# X002X.net
KiCad netlist of a schematic drawn in EAGLE
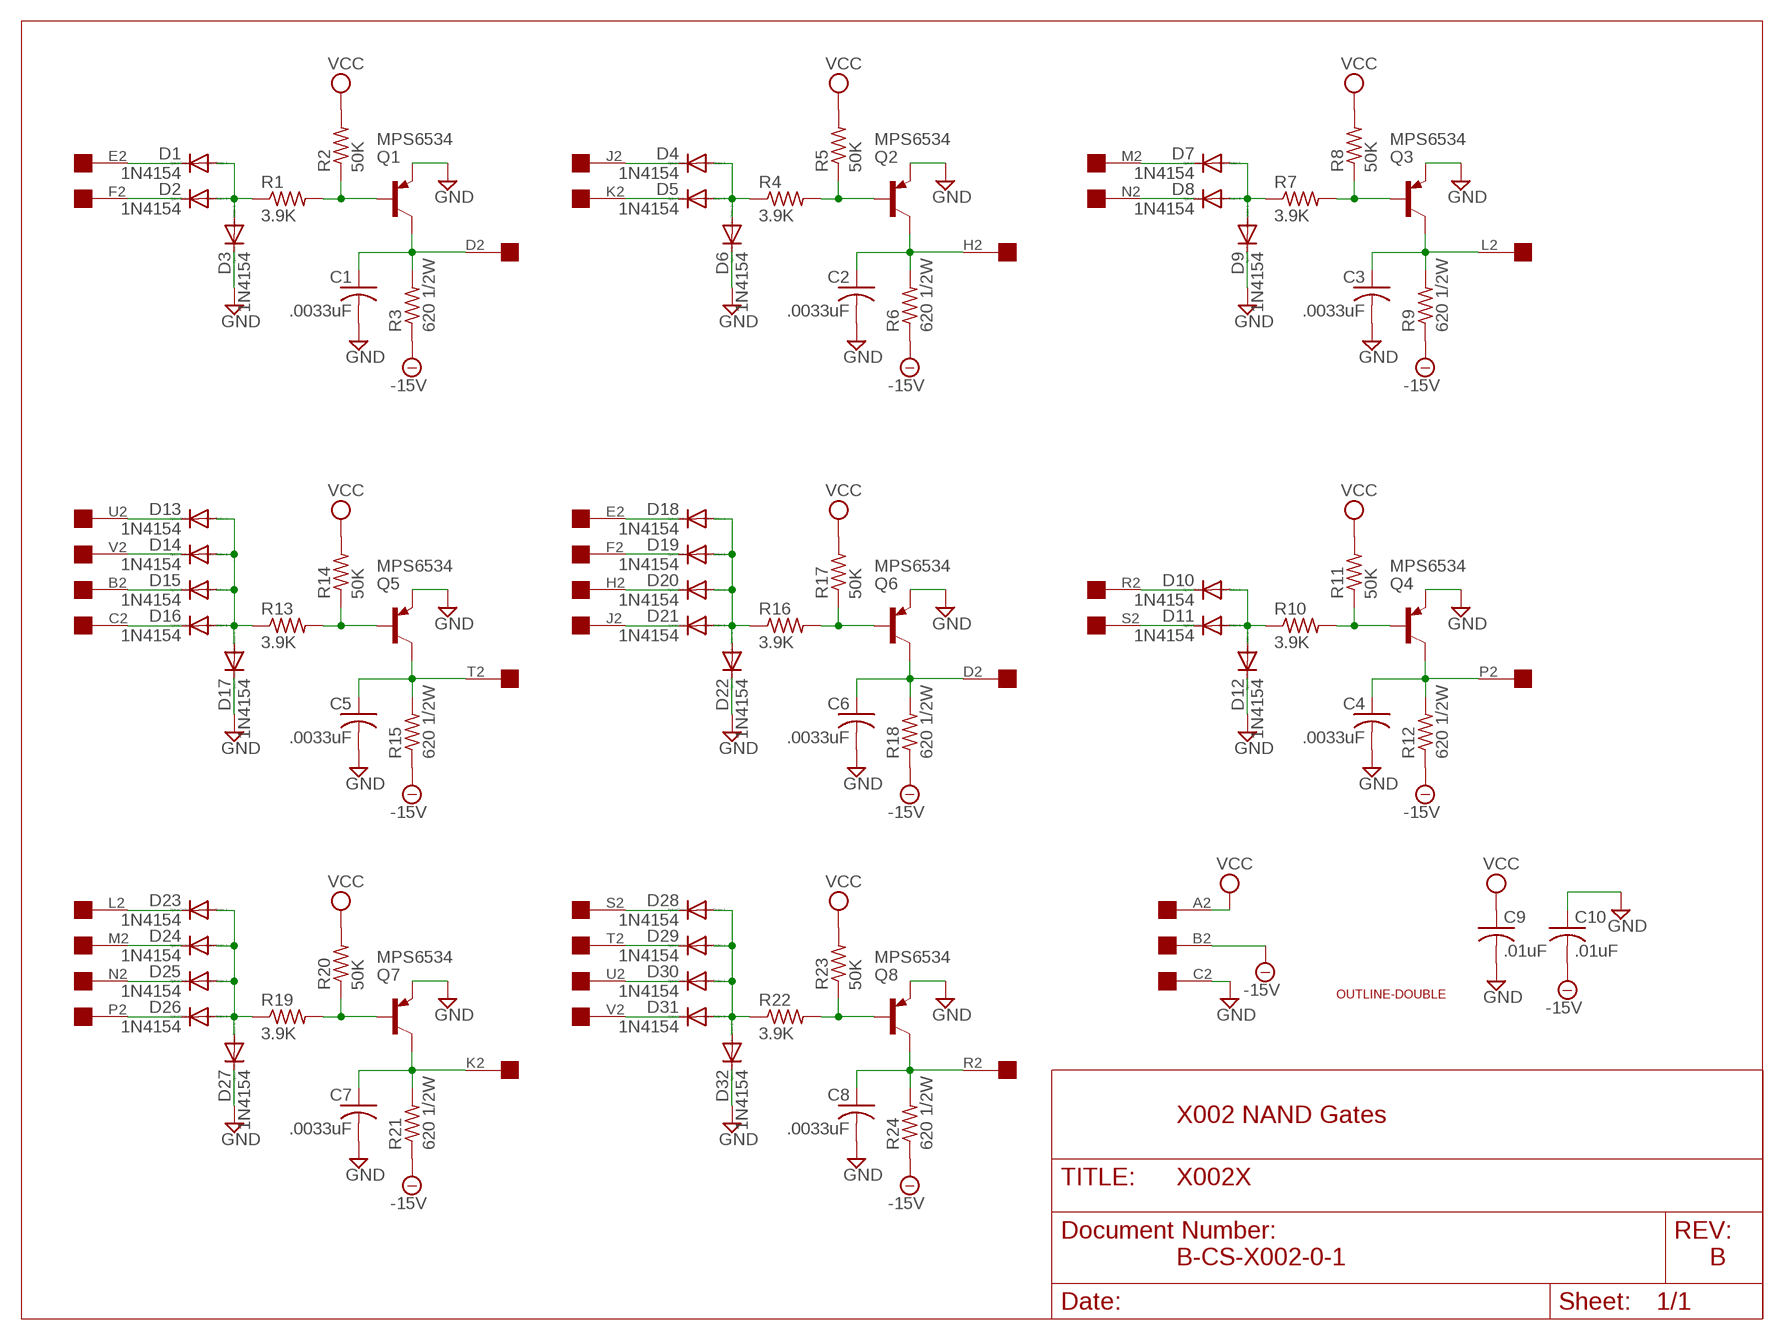
[diagram p0: schematic, sheet 1]

(export (version "E")
  (design (tool "Eeschema 10.0.6"))
  (components
    (comp (ref "A")
      (value "EDGE-1")
      (footprint "eagle-import:EDGE-CON1")
      (libsource (lib "eagle-import") (part "EDGE-1"))
    )
    (comp (ref "B")
      (value "EDGE-1")
      (footprint "eagle-import:EDGE-CON1")
      (libsource (lib "eagle-import") (part "EDGE-1"))
    )
    (comp (ref "C1")
      (value ".0033uF")
      (footprint "eagle-import:C225-062X268")
      (libsource (lib "eagle-import") (part "C-US225-062X268"))
    )
    (comp (ref "C2")
      (value ".0033uF")
      (footprint "eagle-import:C225-062X268")
      (libsource (lib "eagle-import") (part "C-US225-062X268"))
    )
    (comp (ref "C3")
      (value ".0033uF")
      (footprint "eagle-import:C225-062X268")
      (libsource (lib "eagle-import") (part "C-US225-062X268"))
    )
    (comp (ref "C4")
      (value ".0033uF")
      (footprint "eagle-import:C225-062X268")
      (libsource (lib "eagle-import") (part "C-US225-062X268"))
    )
    (comp (ref "C5")
      (value ".0033uF")
      (footprint "eagle-import:C225-062X268")
      (libsource (lib "eagle-import") (part "C-US225-062X268"))
    )
    (comp (ref "C6")
      (value ".0033uF")
      (footprint "eagle-import:C225-062X268")
      (libsource (lib "eagle-import") (part "C-US225-062X268"))
    )
    (comp (ref "C7")
      (value ".0033uF")
      (footprint "eagle-import:C225-062X268")
      (libsource (lib "eagle-import") (part "C-US225-062X268"))
    )
    (comp (ref "C8")
      (value ".0033uF")
      (footprint "eagle-import:C225-062X268")
      (libsource (lib "eagle-import") (part "C-US225-062X268"))
    )
    (comp (ref "C9")
      (value ".01uF")
      (footprint "eagle-import:C050-025X075")
      (libsource (lib "eagle-import") (part "C-US050-025X075"))
    )
    (comp (ref "C10")
      (value ".01uF")
      (footprint "eagle-import:C050-025X075")
      (libsource (lib "eagle-import") (part "C-US050-025X075"))
    )
    (comp (ref "D1")
      (value "1N4154")
      (footprint "eagle-import:DO35-10")
      (libsource (lib "eagle-import") (part "DIODE-DO35-10"))
    )
    (comp (ref "D2")
      (value "1N4154")
      (footprint "eagle-import:DO35-10")
      (libsource (lib "eagle-import") (part "DIODE-DO35-10"))
    )
    (comp (ref "D3")
      (value "1N4154")
      (footprint "eagle-import:DO35-10")
      (libsource (lib "eagle-import") (part "DIODE-DO35-10"))
    )
    (comp (ref "D4")
      (value "1N4154")
      (footprint "eagle-import:DO35-10")
      (libsource (lib "eagle-import") (part "DIODE-DO35-10"))
    )
    (comp (ref "D5")
      (value "1N4154")
      (footprint "eagle-import:DO35-10")
      (libsource (lib "eagle-import") (part "DIODE-DO35-10"))
    )
    (comp (ref "D6")
      (value "1N4154")
      (footprint "eagle-import:DO35-10")
      (libsource (lib "eagle-import") (part "DIODE-DO35-10"))
    )
    (comp (ref "D7")
      (value "1N4154")
      (footprint "eagle-import:DO35-10")
      (libsource (lib "eagle-import") (part "DIODE-DO35-10"))
    )
    (comp (ref "D8")
      (value "1N4154")
      (footprint "eagle-import:DO35-10")
      (libsource (lib "eagle-import") (part "DIODE-DO35-10"))
    )
    (comp (ref "D9")
      (value "1N4154")
      (footprint "eagle-import:DO35-10")
      (libsource (lib "eagle-import") (part "DIODE-DO35-10"))
    )
    (comp (ref "D10")
      (value "1N4154")
      (footprint "eagle-import:DO35-10")
      (libsource (lib "eagle-import") (part "DIODE-DO35-10"))
    )
    (comp (ref "D11")
      (value "1N4154")
      (footprint "eagle-import:DO35-10")
      (libsource (lib "eagle-import") (part "DIODE-DO35-10"))
    )
    (comp (ref "D12")
      (value "1N4154")
      (footprint "eagle-import:DO35-10")
      (libsource (lib "eagle-import") (part "DIODE-DO35-10"))
    )
    (comp (ref "D13")
      (value "1N4154")
      (footprint "eagle-import:DO35-10")
      (libsource (lib "eagle-import") (part "DIODE-DO35-10"))
    )
    (comp (ref "D14")
      (value "1N4154")
      (footprint "eagle-import:DO35-10")
      (libsource (lib "eagle-import") (part "DIODE-DO35-10"))
    )
    (comp (ref "D15")
      (value "1N4154")
      (footprint "eagle-import:DO35-10")
      (libsource (lib "eagle-import") (part "DIODE-DO35-10"))
    )
    (comp (ref "D16")
      (value "1N4154")
      (footprint "eagle-import:DO35-10")
      (libsource (lib "eagle-import") (part "DIODE-DO35-10"))
    )
    (comp (ref "D17")
      (value "1N4154")
      (footprint "eagle-import:DO35-10")
      (libsource (lib "eagle-import") (part "DIODE-DO35-10"))
    )
    (comp (ref "D18")
      (value "1N4154")
      (footprint "eagle-import:DO35-10")
      (libsource (lib "eagle-import") (part "DIODE-DO35-10"))
    )
    (comp (ref "D19")
      (value "1N4154")
      (footprint "eagle-import:DO35-10")
      (libsource (lib "eagle-import") (part "DIODE-DO35-10"))
    )
    (comp (ref "D20")
      (value "1N4154")
      (footprint "eagle-import:DO35-10")
      (libsource (lib "eagle-import") (part "DIODE-DO35-10"))
    )
    (comp (ref "D21")
      (value "1N4154")
      (footprint "eagle-import:DO35-10")
      (libsource (lib "eagle-import") (part "DIODE-DO35-10"))
    )
    (comp (ref "D22")
      (value "1N4154")
      (footprint "eagle-import:DO35-10")
      (libsource (lib "eagle-import") (part "DIODE-DO35-10"))
    )
    (comp (ref "D23")
      (value "1N4154")
      (footprint "eagle-import:DO35-10")
      (libsource (lib "eagle-import") (part "DIODE-DO35-10"))
    )
    (comp (ref "D24")
      (value "1N4154")
      (footprint "eagle-import:DO35-10")
      (libsource (lib "eagle-import") (part "DIODE-DO35-10"))
    )
    (comp (ref "D25")
      (value "1N4154")
      (footprint "eagle-import:DO35-10")
      (libsource (lib "eagle-import") (part "DIODE-DO35-10"))
    )
    (comp (ref "D26")
      (value "1N4154")
      (footprint "eagle-import:DO35-10")
      (libsource (lib "eagle-import") (part "DIODE-DO35-10"))
    )
    (comp (ref "D27")
      (value "1N4154")
      (footprint "eagle-import:DO35-10")
      (libsource (lib "eagle-import") (part "DIODE-DO35-10"))
    )
    (comp (ref "D28")
      (value "1N4154")
      (footprint "eagle-import:DO35-10")
      (libsource (lib "eagle-import") (part "DIODE-DO35-10"))
    )
    (comp (ref "D29")
      (value "1N4154")
      (footprint "eagle-import:DO35-10")
      (libsource (lib "eagle-import") (part "DIODE-DO35-10"))
    )
    (comp (ref "D30")
      (value "1N4154")
      (footprint "eagle-import:DO35-10")
      (libsource (lib "eagle-import") (part "DIODE-DO35-10"))
    )
    (comp (ref "D31")
      (value "1N4154")
      (footprint "eagle-import:DO35-10")
      (libsource (lib "eagle-import") (part "DIODE-DO35-10"))
    )
    (comp (ref "D32")
      (value "1N4154")
      (footprint "eagle-import:DO35-10")
      (libsource (lib "eagle-import") (part "DIODE-DO35-10"))
    )
    (comp (ref "Q1")
      (value "MPS6534")
      (footprint "eagle-import:TO5")
      (libsource (lib "eagle-import") (part "-PNP-TO5"))
    )
    (comp (ref "Q2")
      (value "MPS6534")
      (footprint "eagle-import:TO5")
      (libsource (lib "eagle-import") (part "-PNP-TO5"))
    )
    (comp (ref "Q3")
      (value "MPS6534")
      (footprint "eagle-import:TO5")
      (libsource (lib "eagle-import") (part "-PNP-TO5"))
    )
    (comp (ref "Q4")
      (value "MPS6534")
      (footprint "eagle-import:TO5")
      (libsource (lib "eagle-import") (part "-PNP-TO5"))
    )
    (comp (ref "Q5")
      (value "MPS6534")
      (footprint "eagle-import:TO5")
      (libsource (lib "eagle-import") (part "-PNP-TO5"))
    )
    (comp (ref "Q6")
      (value "MPS6534")
      (footprint "eagle-import:TO5")
      (libsource (lib "eagle-import") (part "-PNP-TO5"))
    )
    (comp (ref "Q7")
      (value "MPS6534")
      (footprint "eagle-import:TO5")
      (libsource (lib "eagle-import") (part "-PNP-TO5"))
    )
    (comp (ref "Q8")
      (value "MPS6534")
      (footprint "eagle-import:TO5")
      (libsource (lib "eagle-import") (part "-PNP-TO5"))
    )
    (comp (ref "R1")
      (value "3.9K")
      (footprint "eagle-import:0207_10")
      (libsource (lib "eagle-import") (part "R-US_0207/10"))
    )
    (comp (ref "R2")
      (value "50K")
      (footprint "eagle-import:0207_10")
      (libsource (lib "eagle-import") (part "R-US_0207/10"))
    )
    (comp (ref "R3")
      (value "620 1/2W")
      (footprint "eagle-import:0414_15")
      (libsource (lib "eagle-import") (part "R-US_0414/15"))
    )
    (comp (ref "R4")
      (value "3.9K")
      (footprint "eagle-import:0207_10")
      (libsource (lib "eagle-import") (part "R-US_0207/10"))
    )
    (comp (ref "R5")
      (value "50K")
      (footprint "eagle-import:0207_10")
      (libsource (lib "eagle-import") (part "R-US_0207/10"))
    )
    (comp (ref "R6")
      (value "620 1/2W")
      (footprint "eagle-import:0414_15")
      (libsource (lib "eagle-import") (part "R-US_0414/15"))
    )
    (comp (ref "R7")
      (value "3.9K")
      (footprint "eagle-import:0207_10")
      (libsource (lib "eagle-import") (part "R-US_0207/10"))
    )
    (comp (ref "R8")
      (value "50K")
      (footprint "eagle-import:0207_10")
      (libsource (lib "eagle-import") (part "R-US_0207/10"))
    )
    (comp (ref "R9")
      (value "620 1/2W")
      (footprint "eagle-import:0414_15")
      (libsource (lib "eagle-import") (part "R-US_0414/15"))
    )
    (comp (ref "R10")
      (value "3.9K")
      (footprint "eagle-import:0207_10")
      (libsource (lib "eagle-import") (part "R-US_0207/10"))
    )
    (comp (ref "R11")
      (value "50K")
      (footprint "eagle-import:0207_10")
      (libsource (lib "eagle-import") (part "R-US_0207/10"))
    )
    (comp (ref "R12")
      (value "620 1/2W")
      (footprint "eagle-import:0414_15")
      (libsource (lib "eagle-import") (part "R-US_0414/15"))
    )
    (comp (ref "R13")
      (value "3.9K")
      (footprint "eagle-import:0207_10")
      (libsource (lib "eagle-import") (part "R-US_0207/10"))
    )
    (comp (ref "R14")
      (value "50K")
      (footprint "eagle-import:0207_10")
      (libsource (lib "eagle-import") (part "R-US_0207/10"))
    )
    (comp (ref "R15")
      (value "620 1/2W")
      (footprint "eagle-import:0414_15")
      (libsource (lib "eagle-import") (part "R-US_0414/15"))
    )
    (comp (ref "R16")
      (value "3.9K")
      (footprint "eagle-import:0207_10")
      (libsource (lib "eagle-import") (part "R-US_0207/10"))
    )
    (comp (ref "R17")
      (value "50K")
      (footprint "eagle-import:0207_10")
      (libsource (lib "eagle-import") (part "R-US_0207/10"))
    )
    (comp (ref "R18")
      (value "620 1/2W")
      (footprint "eagle-import:0414_15")
      (libsource (lib "eagle-import") (part "R-US_0414/15"))
    )
    (comp (ref "R19")
      (value "3.9K")
      (footprint "eagle-import:0207_10")
      (libsource (lib "eagle-import") (part "R-US_0207/10"))
    )
    (comp (ref "R20")
      (value "50K")
      (footprint "eagle-import:0207_10")
      (libsource (lib "eagle-import") (part "R-US_0207/10"))
    )
    (comp (ref "R21")
      (value "620 1/2W")
      (footprint "eagle-import:0414_15")
      (libsource (lib "eagle-import") (part "R-US_0414/15"))
    )
    (comp (ref "R22")
      (value "3.9K")
      (footprint "eagle-import:0207_10")
      (libsource (lib "eagle-import") (part "R-US_0207/10"))
    )
    (comp (ref "R23")
      (value "50K")
      (footprint "eagle-import:0207_10")
      (libsource (lib "eagle-import") (part "R-US_0207/10"))
    )
    (comp (ref "R24")
      (value "620 1/2W")
      (footprint "eagle-import:0414_15")
      (libsource (lib "eagle-import") (part "R-US_0414/15"))
    )
    (comp (ref "U$1")
      (value "OUTLINE-DOUBLE")
      (footprint "eagle-import:DOUBLE")
      (libsource (lib "eagle-import") (part "OUTLINE-DOUBLE"))
    )
  )
  (nets
    (net (code "1") (name "-15V") (class "Default")
      (node (ref "A") (pin "B2") (pinfunction "1_B2") (pintype "bidirectional"))
      (node (ref "C10") (pin "2") (pinfunction "2_2") (pintype "passive"))
      (node (ref "R12") (pin "1") (pinfunction "1_1") (pintype "passive"))
      (node (ref "R15") (pin "1") (pinfunction "1_1") (pintype "passive"))
      (node (ref "R18") (pin "1") (pinfunction "1_1") (pintype "passive"))
      (node (ref "R21") (pin "1") (pinfunction "1_1") (pintype "passive"))
      (node (ref "R24") (pin "1") (pinfunction "1_1") (pintype "passive"))
      (node (ref "R3") (pin "1") (pinfunction "1_1") (pintype "passive"))
      (node (ref "R6") (pin "1") (pinfunction "1_1") (pintype "passive"))
      (node (ref "R9") (pin "1") (pinfunction "1_1") (pintype "passive"))
    )
    (net (code "2") (name "GND") (class "Default")
      (node (ref "A") (pin "C2") (pinfunction "1_C2") (pintype "bidirectional"))
      (node (ref "C1") (pin "2") (pinfunction "2_2") (pintype "passive"))
      (node (ref "C10") (pin "1") (pinfunction "1_1") (pintype "passive"))
      (node (ref "C2") (pin "2") (pinfunction "2_2") (pintype "passive"))
      (node (ref "C3") (pin "2") (pinfunction "2_2") (pintype "passive"))
      (node (ref "C4") (pin "2") (pinfunction "2_2") (pintype "passive"))
      (node (ref "C5") (pin "2") (pinfunction "2_2") (pintype "passive"))
      (node (ref "C6") (pin "2") (pinfunction "2_2") (pintype "passive"))
      (node (ref "C7") (pin "2") (pinfunction "2_2") (pintype "passive"))
      (node (ref "C8") (pin "2") (pinfunction "2_2") (pintype "passive"))
      (node (ref "C9") (pin "2") (pinfunction "2_2") (pintype "passive"))
      (node (ref "D12") (pin "C") (pinfunction "C_C") (pintype "passive"))
      (node (ref "D17") (pin "C") (pinfunction "C_C") (pintype "passive"))
      (node (ref "D22") (pin "C") (pinfunction "C_C") (pintype "passive"))
      (node (ref "D27") (pin "C") (pinfunction "C_C") (pintype "passive"))
      (node (ref "D3") (pin "C") (pinfunction "C_C") (pintype "passive"))
      (node (ref "D32") (pin "C") (pinfunction "C_C") (pintype "passive"))
      (node (ref "D6") (pin "C") (pinfunction "C_C") (pintype "passive"))
      (node (ref "D9") (pin "C") (pinfunction "C_C") (pintype "passive"))
      (node (ref "Q1") (pin "1") (pinfunction "E_1") (pintype "passive"))
      (node (ref "Q2") (pin "1") (pinfunction "E_1") (pintype "passive"))
      (node (ref "Q3") (pin "1") (pinfunction "E_1") (pintype "passive"))
      (node (ref "Q4") (pin "1") (pinfunction "E_1") (pintype "passive"))
      (node (ref "Q5") (pin "1") (pinfunction "E_1") (pintype "passive"))
      (node (ref "Q6") (pin "1") (pinfunction "E_1") (pintype "passive"))
      (node (ref "Q7") (pin "1") (pinfunction "E_1") (pintype "passive"))
      (node (ref "Q8") (pin "1") (pinfunction "E_1") (pintype "passive"))
    )
    (net (code "3") (name "Net-(AD-1)") (class "Default")
      (node (ref "A") (pin "D2") (pinfunction "1_D2") (pintype "bidirectional"))
      (node (ref "C1") (pin "1") (pinfunction "1_1") (pintype "passive"))
      (node (ref "Q1") (pin "3") (pinfunction "C_3") (pintype "passive"))
      (node (ref "R3") (pin "2") (pinfunction "2_2") (pintype "passive"))
    )
    (net (code "4") (name "Net-(AE-1)") (class "Default")
      (node (ref "A") (pin "E2") (pinfunction "1_E2") (pintype "bidirectional"))
      (node (ref "D1") (pin "C") (pinfunction "C_C") (pintype "passive"))
    )
    (net (code "5") (name "Net-(AF-1)") (class "Default")
      (node (ref "A") (pin "F2") (pinfunction "1_F2") (pintype "bidirectional"))
      (node (ref "D2") (pin "C") (pinfunction "C_C") (pintype "passive"))
    )
    (net (code "6") (name "Net-(AG-1)") (class "Default")
      (node (ref "A") (pin "H2") (pinfunction "1_H2") (pintype "bidirectional"))
      (node (ref "C2") (pin "1") (pinfunction "1_1") (pintype "passive"))
      (node (ref "Q2") (pin "3") (pinfunction "C_3") (pintype "passive"))
      (node (ref "R6") (pin "2") (pinfunction "2_2") (pintype "passive"))
    )
    (net (code "7") (name "Net-(AH-1)") (class "Default")
      (node (ref "A") (pin "J2") (pinfunction "1_J2") (pintype "bidirectional"))
      (node (ref "D4") (pin "C") (pinfunction "C_C") (pintype "passive"))
    )
    (net (code "8") (name "Net-(AI-1)") (class "Default")
      (node (ref "A") (pin "K2") (pinfunction "1_K2") (pintype "bidirectional"))
      (node (ref "D5") (pin "C") (pinfunction "C_C") (pintype "passive"))
    )
    (net (code "9") (name "Net-(AJ-1)") (class "Default")
      (node (ref "A") (pin "L2") (pinfunction "1_L2") (pintype "bidirectional"))
      (node (ref "C3") (pin "1") (pinfunction "1_1") (pintype "passive"))
      (node (ref "Q3") (pin "3") (pinfunction "C_3") (pintype "passive"))
      (node (ref "R9") (pin "2") (pinfunction "2_2") (pintype "passive"))
    )
    (net (code "10") (name "Net-(AK-1)") (class "Default")
      (node (ref "A") (pin "M2") (pinfunction "1_M2") (pintype "bidirectional"))
      (node (ref "D7") (pin "C") (pinfunction "C_C") (pintype "passive"))
    )
    (net (code "11") (name "Net-(AL-1)") (class "Default")
      (node (ref "A") (pin "N2") (pinfunction "1_N2") (pintype "bidirectional"))
      (node (ref "D8") (pin "C") (pinfunction "C_C") (pintype "passive"))
    )
    (net (code "12") (name "Net-(AM-1)") (class "Default")
      (node (ref "A") (pin "P2") (pinfunction "1_P2") (pintype "bidirectional"))
      (node (ref "C4") (pin "1") (pinfunction "1_1") (pintype "passive"))
      (node (ref "Q4") (pin "3") (pinfunction "C_3") (pintype "passive"))
      (node (ref "R12") (pin "2") (pinfunction "2_2") (pintype "passive"))
    )
    (net (code "13") (name "Net-(AN-1)") (class "Default")
      (node (ref "A") (pin "R2") (pinfunction "1_R2") (pintype "bidirectional"))
      (node (ref "D10") (pin "C") (pinfunction "C_C") (pintype "passive"))
    )
    (net (code "14") (name "Net-(AO-1)") (class "Default")
      (node (ref "A") (pin "S2") (pinfunction "1_S2") (pintype "bidirectional"))
      (node (ref "D11") (pin "C") (pinfunction "C_C") (pintype "passive"))
    )
    (net (code "15") (name "Net-(AP-1)") (class "Default")
      (node (ref "A") (pin "T2") (pinfunction "1_T2") (pintype "bidirectional"))
      (node (ref "C5") (pin "1") (pinfunction "1_1") (pintype "passive"))
      (node (ref "Q5") (pin "3") (pinfunction "C_3") (pintype "passive"))
      (node (ref "R15") (pin "2") (pinfunction "2_2") (pintype "passive"))
    )
    (net (code "16") (name "Net-(AQ-1)") (class "Default")
      (node (ref "A") (pin "U2") (pinfunction "1_U2") (pintype "bidirectional"))
      (node (ref "D13") (pin "C") (pinfunction "C_C") (pintype "passive"))
    )
    (net (code "17") (name "Net-(AR-1)") (class "Default")
      (node (ref "A") (pin "V2") (pinfunction "1_V2") (pintype "bidirectional"))
      (node (ref "D14") (pin "C") (pinfunction "C_C") (pintype "passive"))
    )
    (net (code "18") (name "Net-(BB-1)") (class "Default")
      (node (ref "B") (pin "B2") (pinfunction "1_B2") (pintype "bidirectional"))
      (node (ref "D15") (pin "C") (pinfunction "C_C") (pintype "passive"))
    )
    (net (code "19") (name "Net-(BC-1)") (class "Default")
      (node (ref "B") (pin "C2") (pinfunction "1_C2") (pintype "bidirectional"))
      (node (ref "D16") (pin "C") (pinfunction "C_C") (pintype "passive"))
    )
    (net (code "20") (name "Net-(BD-1)") (class "Default")
      (node (ref "B") (pin "D2") (pinfunction "1_D2") (pintype "bidirectional"))
      (node (ref "C6") (pin "1") (pinfunction "1_1") (pintype "passive"))
      (node (ref "Q6") (pin "3") (pinfunction "C_3") (pintype "passive"))
      (node (ref "R18") (pin "2") (pinfunction "2_2") (pintype "passive"))
    )
    (net (code "21") (name "Net-(BE-1)") (class "Default")
      (node (ref "B") (pin "E2") (pinfunction "1_E2") (pintype "bidirectional"))
      (node (ref "D18") (pin "C") (pinfunction "C_C") (pintype "passive"))
    )
    (net (code "22") (name "Net-(BF-1)") (class "Default")
      (node (ref "B") (pin "F2") (pinfunction "1_F2") (pintype "bidirectional"))
      (node (ref "D19") (pin "C") (pinfunction "C_C") (pintype "passive"))
    )
    (net (code "23") (name "Net-(BG-1)") (class "Default")
      (node (ref "B") (pin "H2") (pinfunction "1_H2") (pintype "bidirectional"))
      (node (ref "D20") (pin "C") (pinfunction "C_C") (pintype "passive"))
    )
    (net (code "24") (name "Net-(BH-1)") (class "Default")
      (node (ref "B") (pin "J2") (pinfunction "1_J2") (pintype "bidirectional"))
      (node (ref "D21") (pin "C") (pinfunction "C_C") (pintype "passive"))
    )
    (net (code "25") (name "Net-(BI-1)") (class "Default")
      (node (ref "B") (pin "K2") (pinfunction "1_K2") (pintype "bidirectional"))
      (node (ref "C7") (pin "1") (pinfunction "1_1") (pintype "passive"))
      (node (ref "Q7") (pin "3") (pinfunction "C_3") (pintype "passive"))
      (node (ref "R21") (pin "2") (pinfunction "2_2") (pintype "passive"))
    )
    (net (code "26") (name "Net-(BJ-1)") (class "Default")
      (node (ref "B") (pin "L2") (pinfunction "1_L2") (pintype "bidirectional"))
      (node (ref "D23") (pin "C") (pinfunction "C_C") (pintype "passive"))
    )
    (net (code "27") (name "Net-(BK-1)") (class "Default")
      (node (ref "B") (pin "M2") (pinfunction "1_M2") (pintype "bidirectional"))
      (node (ref "D24") (pin "C") (pinfunction "C_C") (pintype "passive"))
    )
    (net (code "28") (name "Net-(BL-1)") (class "Default")
      (node (ref "B") (pin "N2") (pinfunction "1_N2") (pintype "bidirectional"))
      (node (ref "D25") (pin "C") (pinfunction "C_C") (pintype "passive"))
    )
    (net (code "29") (name "Net-(BM-1)") (class "Default")
      (node (ref "B") (pin "P2") (pinfunction "1_P2") (pintype "bidirectional"))
      (node (ref "D26") (pin "C") (pinfunction "C_C") (pintype "passive"))
    )
    (net (code "30") (name "Net-(BN-1)") (class "Default")
      (node (ref "B") (pin "R2") (pinfunction "1_R2") (pintype "bidirectional"))
      (node (ref "C8") (pin "1") (pinfunction "1_1") (pintype "passive"))
      (node (ref "Q8") (pin "3") (pinfunction "C_3") (pintype "passive"))
      (node (ref "R24") (pin "2") (pinfunction "2_2") (pintype "passive"))
    )
    (net (code "31") (name "Net-(BO-1)") (class "Default")
      (node (ref "B") (pin "S2") (pinfunction "1_S2") (pintype "bidirectional"))
      (node (ref "D28") (pin "C") (pinfunction "C_C") (pintype "passive"))
    )
    (net (code "32") (name "Net-(BP-1)") (class "Default")
      (node (ref "B") (pin "T2") (pinfunction "1_T2") (pintype "bidirectional"))
      (node (ref "D29") (pin "C") (pinfunction "C_C") (pintype "passive"))
    )
    (net (code "33") (name "Net-(BQ-1)") (class "Default")
      (node (ref "B") (pin "U2") (pinfunction "1_U2") (pintype "bidirectional"))
      (node (ref "D30") (pin "C") (pinfunction "C_C") (pintype "passive"))
    )
    (net (code "34") (name "Net-(BR-1)") (class "Default")
      (node (ref "B") (pin "V2") (pinfunction "1_V2") (pintype "bidirectional"))
      (node (ref "D31") (pin "C") (pinfunction "C_C") (pintype "passive"))
    )
    (net (code "35") (name "Net-(D1-PadA)") (class "Default")
      (node (ref "D1") (pin "A") (pinfunction "A_A") (pintype "passive"))
      (node (ref "D2") (pin "A") (pinfunction "A_A") (pintype "passive"))
      (node (ref "D3") (pin "A") (pinfunction "A_A") (pintype "passive"))
      (node (ref "R1") (pin "1") (pinfunction "1_1") (pintype "passive"))
    )
    (net (code "36") (name "Net-(D4-PadA)") (class "Default")
      (node (ref "D4") (pin "A") (pinfunction "A_A") (pintype "passive"))
      (node (ref "D5") (pin "A") (pinfunction "A_A") (pintype "passive"))
      (node (ref "D6") (pin "A") (pinfunction "A_A") (pintype "passive"))
      (node (ref "R4") (pin "1") (pinfunction "1_1") (pintype "passive"))
    )
    (net (code "37") (name "Net-(D7-PadA)") (class "Default")
      (node (ref "D7") (pin "A") (pinfunction "A_A") (pintype "passive"))
      (node (ref "D8") (pin "A") (pinfunction "A_A") (pintype "passive"))
      (node (ref "D9") (pin "A") (pinfunction "A_A") (pintype "passive"))
      (node (ref "R7") (pin "1") (pinfunction "1_1") (pintype "passive"))
    )
    (net (code "38") (name "Net-(D10-PadA)") (class "Default")
      (node (ref "D10") (pin "A") (pinfunction "A_A") (pintype "passive"))
      (node (ref "D11") (pin "A") (pinfunction "A_A") (pintype "passive"))
      (node (ref "D12") (pin "A") (pinfunction "A_A") (pintype "passive"))
      (node (ref "R10") (pin "1") (pinfunction "1_1") (pintype "passive"))
    )
    (net (code "39") (name "Net-(D13-PadA)") (class "Default")
      (node (ref "D13") (pin "A") (pinfunction "A_A") (pintype "passive"))
      (node (ref "D14") (pin "A") (pinfunction "A_A") (pintype "passive"))
      (node (ref "D15") (pin "A") (pinfunction "A_A") (pintype "passive"))
      (node (ref "D16") (pin "A") (pinfunction "A_A") (pintype "passive"))
      (node (ref "D17") (pin "A") (pinfunction "A_A") (pintype "passive"))
      (node (ref "R13") (pin "1") (pinfunction "1_1") (pintype "passive"))
    )
    (net (code "40") (name "Net-(D18-PadA)") (class "Default")
      (node (ref "D18") (pin "A") (pinfunction "A_A") (pintype "passive"))
      (node (ref "D19") (pin "A") (pinfunction "A_A") (pintype "passive"))
      (node (ref "D20") (pin "A") (pinfunction "A_A") (pintype "passive"))
      (node (ref "D21") (pin "A") (pinfunction "A_A") (pintype "passive"))
      (node (ref "D22") (pin "A") (pinfunction "A_A") (pintype "passive"))
      (node (ref "R16") (pin "1") (pinfunction "1_1") (pintype "passive"))
    )
    (net (code "41") (name "Net-(D23-PadA)") (class "Default")
      (node (ref "D23") (pin "A") (pinfunction "A_A") (pintype "passive"))
      (node (ref "D24") (pin "A") (pinfunction "A_A") (pintype "passive"))
      (node (ref "D25") (pin "A") (pinfunction "A_A") (pintype "passive"))
      (node (ref "D26") (pin "A") (pinfunction "A_A") (pintype "passive"))
      (node (ref "D27") (pin "A") (pinfunction "A_A") (pintype "passive"))
      (node (ref "R19") (pin "1") (pinfunction "1_1") (pintype "passive"))
    )
    (net (code "42") (name "Net-(D28-PadA)") (class "Default")
      (node (ref "D28") (pin "A") (pinfunction "A_A") (pintype "passive"))
      (node (ref "D29") (pin "A") (pinfunction "A_A") (pintype "passive"))
      (node (ref "D30") (pin "A") (pinfunction "A_A") (pintype "passive"))
      (node (ref "D31") (pin "A") (pinfunction "A_A") (pintype "passive"))
      (node (ref "D32") (pin "A") (pinfunction "A_A") (pintype "passive"))
      (node (ref "R22") (pin "1") (pinfunction "1_1") (pintype "passive"))
    )
    (net (code "43") (name "Net-(Q1-B)") (class "Default")
      (node (ref "Q1") (pin "2") (pinfunction "B_2") (pintype "passive"))
      (node (ref "R1") (pin "2") (pinfunction "2_2") (pintype "passive"))
      (node (ref "R2") (pin "1") (pinfunction "1_1") (pintype "passive"))
    )
    (net (code "44") (name "Net-(Q2-B)") (class "Default")
      (node (ref "Q2") (pin "2") (pinfunction "B_2") (pintype "passive"))
      (node (ref "R4") (pin "2") (pinfunction "2_2") (pintype "passive"))
      (node (ref "R5") (pin "1") (pinfunction "1_1") (pintype "passive"))
    )
    (net (code "45") (name "Net-(Q3-B)") (class "Default")
      (node (ref "Q3") (pin "2") (pinfunction "B_2") (pintype "passive"))
      (node (ref "R7") (pin "2") (pinfunction "2_2") (pintype "passive"))
      (node (ref "R8") (pin "1") (pinfunction "1_1") (pintype "passive"))
    )
    (net (code "46") (name "Net-(Q4-B)") (class "Default")
      (node (ref "Q4") (pin "2") (pinfunction "B_2") (pintype "passive"))
      (node (ref "R10") (pin "2") (pinfunction "2_2") (pintype "passive"))
      (node (ref "R11") (pin "1") (pinfunction "1_1") (pintype "passive"))
    )
    (net (code "47") (name "Net-(Q5-B)") (class "Default")
      (node (ref "Q5") (pin "2") (pinfunction "B_2") (pintype "passive"))
      (node (ref "R13") (pin "2") (pinfunction "2_2") (pintype "passive"))
      (node (ref "R14") (pin "1") (pinfunction "1_1") (pintype "passive"))
    )
    (net (code "48") (name "Net-(Q6-B)") (class "Default")
      (node (ref "Q6") (pin "2") (pinfunction "B_2") (pintype "passive"))
      (node (ref "R16") (pin "2") (pinfunction "2_2") (pintype "passive"))
      (node (ref "R17") (pin "1") (pinfunction "1_1") (pintype "passive"))
    )
    (net (code "49") (name "Net-(Q7-B)") (class "Default")
      (node (ref "Q7") (pin "2") (pinfunction "B_2") (pintype "passive"))
      (node (ref "R19") (pin "2") (pinfunction "2_2") (pintype "passive"))
      (node (ref "R20") (pin "1") (pinfunction "1_1") (pintype "passive"))
    )
    (net (code "50") (name "Net-(Q8-B)") (class "Default")
      (node (ref "Q8") (pin "2") (pinfunction "B_2") (pintype "passive"))
      (node (ref "R22") (pin "2") (pinfunction "2_2") (pintype "passive"))
      (node (ref "R23") (pin "1") (pinfunction "1_1") (pintype "passive"))
    )
    (net (code "51") (name "VCC") (class "Default")
      (node (ref "A") (pin "A2") (pinfunction "1_A2") (pintype "bidirectional"))
      (node (ref "C9") (pin "1") (pinfunction "1_1") (pintype "passive"))
      (node (ref "R11") (pin "2") (pinfunction "2_2") (pintype "passive"))
      (node (ref "R14") (pin "2") (pinfunction "2_2") (pintype "passive"))
      (node (ref "R17") (pin "2") (pinfunction "2_2") (pintype "passive"))
      (node (ref "R2") (pin "2") (pinfunction "2_2") (pintype "passive"))
      (node (ref "R20") (pin "2") (pinfunction "2_2") (pintype "passive"))
      (node (ref "R23") (pin "2") (pinfunction "2_2") (pintype "passive"))
      (node (ref "R5") (pin "2") (pinfunction "2_2") (pintype "passive"))
      (node (ref "R8") (pin "2") (pinfunction "2_2") (pintype "passive"))
    )
  )
)
